# SCH_Atmega328-Dev_Board_v0_1_2022-11-11.net
KiCad netlist of a schematic drawn in EasyEDA
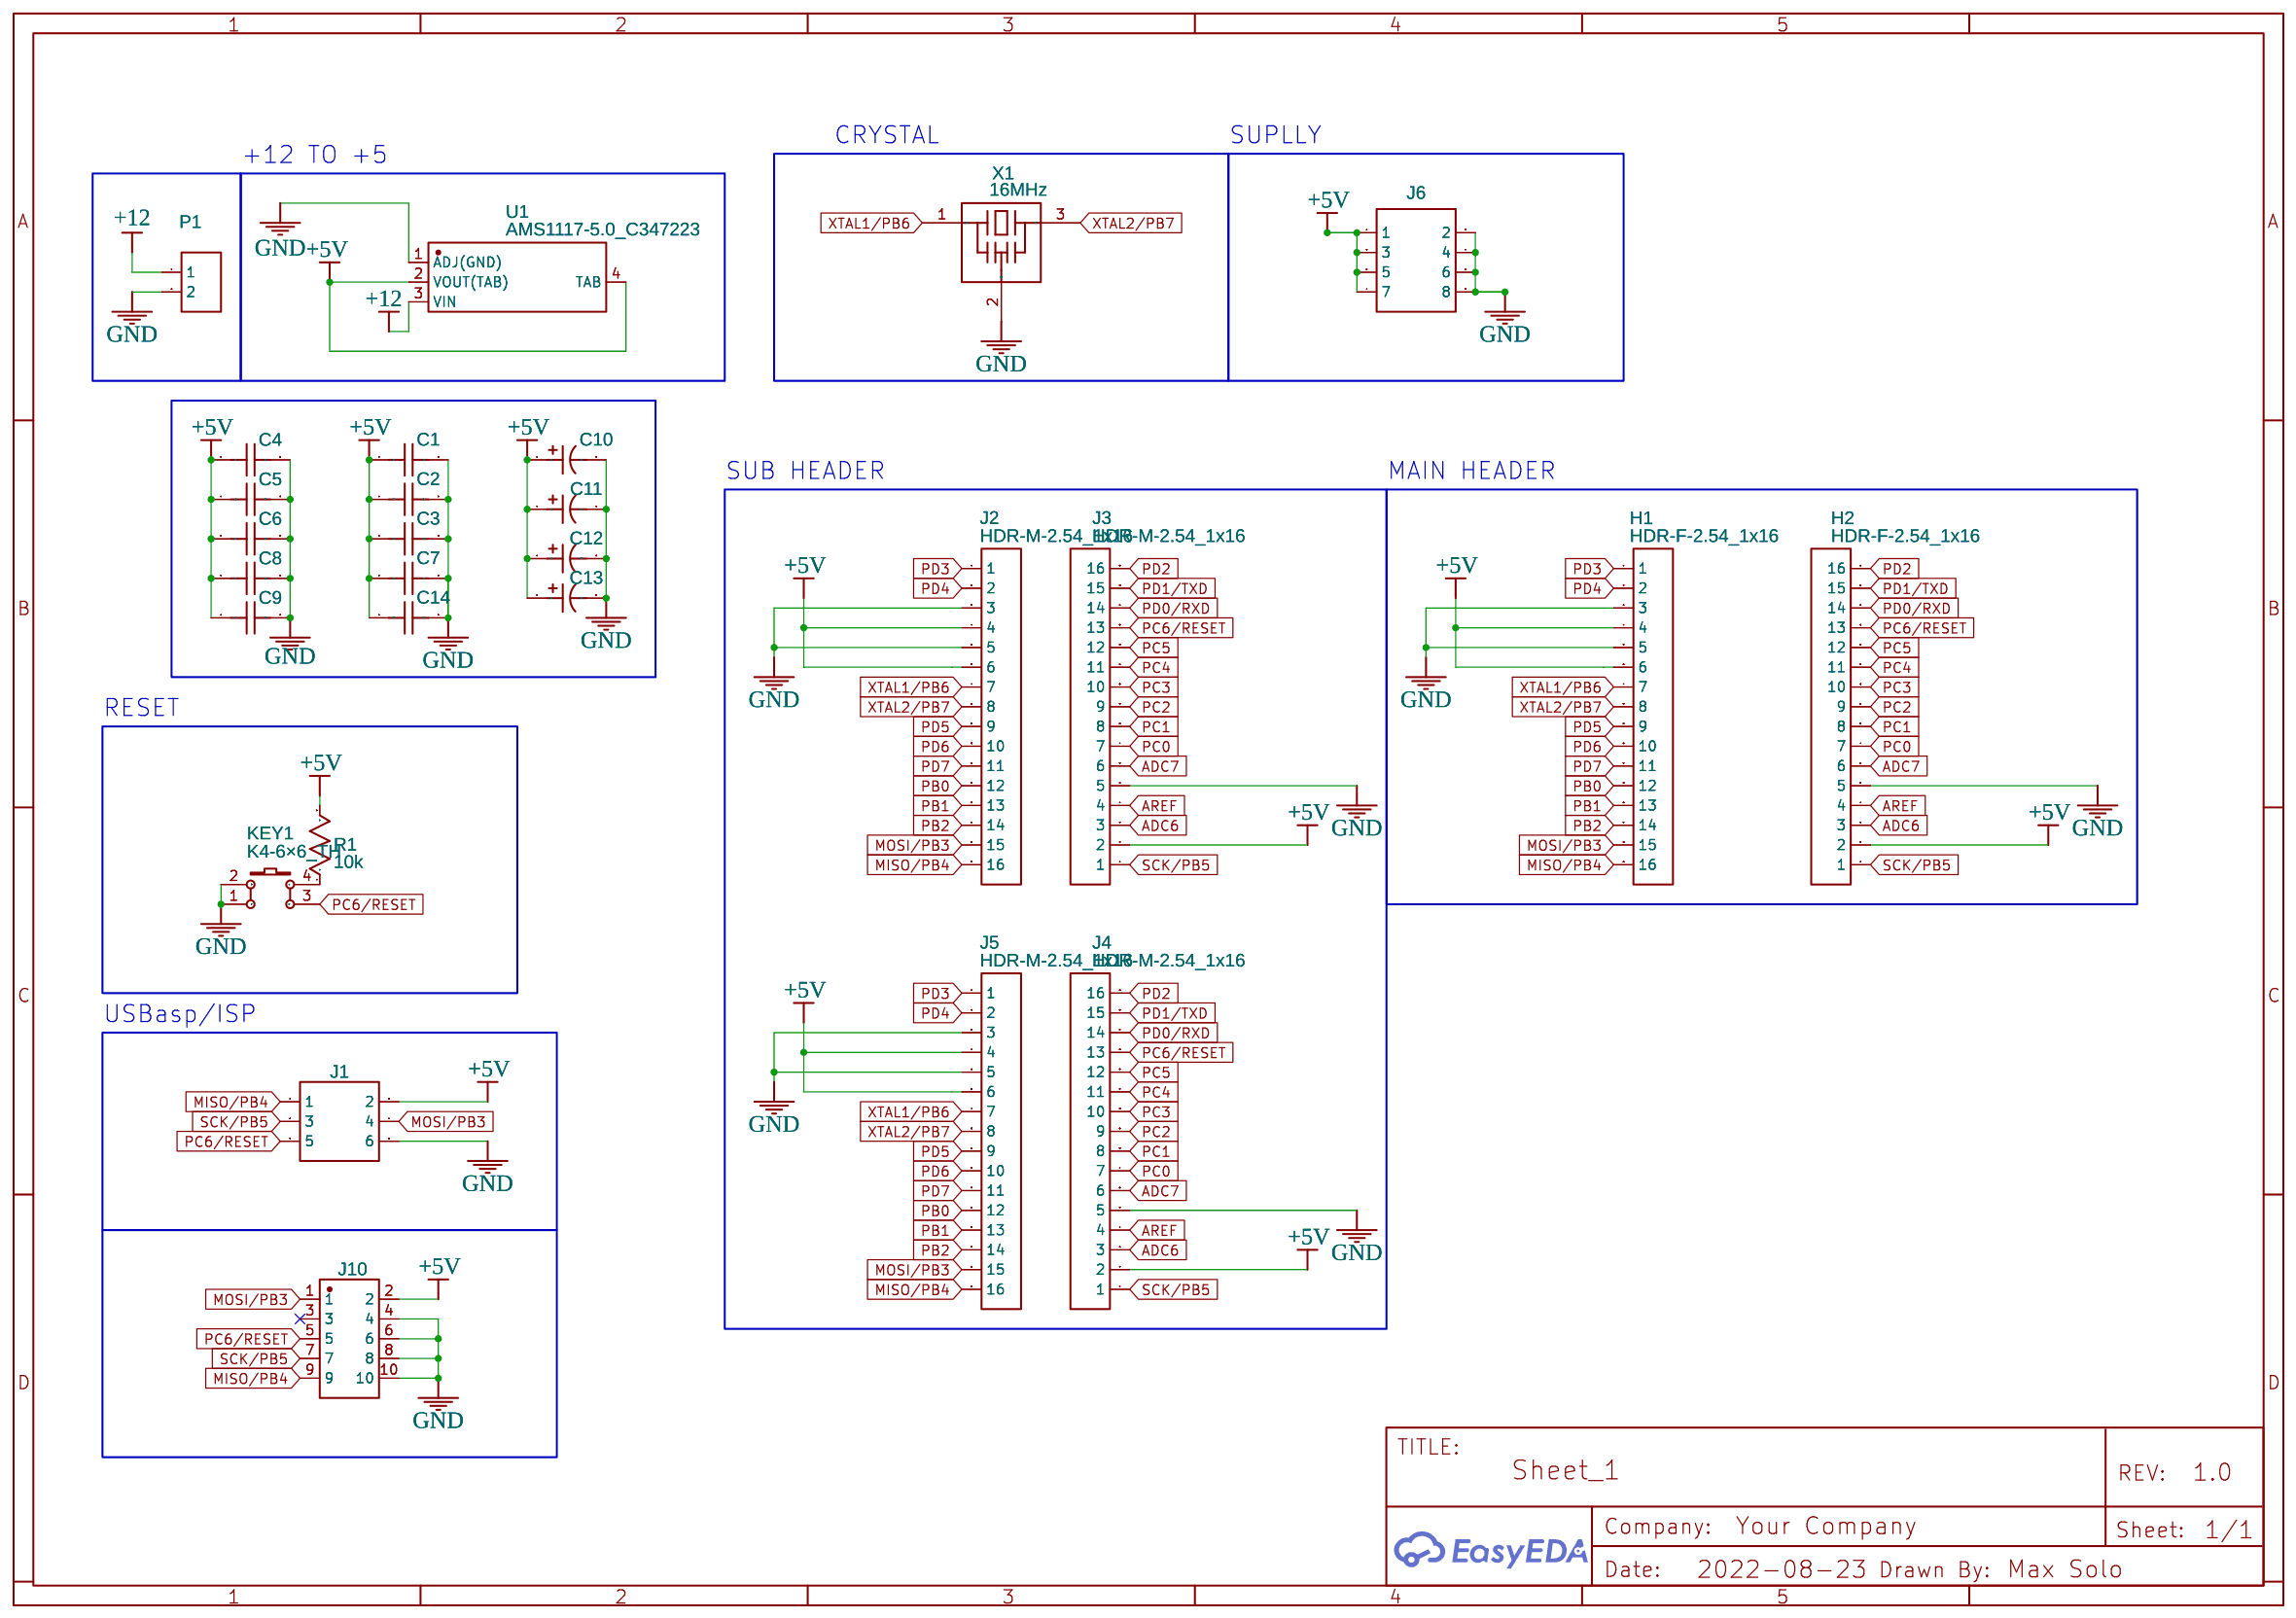
[diagram p0: schematic sheet]

(export (version "E")
  (design (tool "Eeschema 10.0.6"))
  (components
    (comp (ref "C1") (value "200uF") (libsource (lib "") (part "C_0805_US")))
    (comp (ref "C2") (value "200uF") (libsource (lib "") (part "C_0805_US")))
    (comp (ref "C3") (value "200uF") (libsource (lib "") (part "C_0805_US")))
    (comp (ref "C4") (value "200uF") (libsource (lib "") (part "C_0805_US")))
    (comp (ref "C5") (value "200uF") (libsource (lib "") (part "C_0805_US")))
    (comp (ref "C6") (value "200uF") (libsource (lib "") (part "C_0805_US")))
    (comp (ref "C7") (value "0.1u") (libsource (lib "") (part "C_0805_US")))
    (comp (ref "C8") (value "200uF") (libsource (lib "") (part "C_0805_US")))
    (comp (ref "C9") (value "200uF") (libsource (lib "") (part "C_0805_US")))
    (comp (ref "C10")
      (value "330uF")
      (fields
        (field (name "BOM_Manufacturer Part") "SPT1AM331E07OR")
        (field (name "BOM_Supplier Part") "C697724")
      )
      (libsource (lib "") (part "SPT1AM331E07OR"))
    )
    (comp (ref "C11")
      (value "330uF")
      (fields
        (field (name "BOM_Manufacturer Part") "SPT1AM331E07OR")
        (field (name "BOM_Supplier Part") "C697724")
      )
      (libsource (lib "") (part "SPT1AM331E07OR"))
    )
    (comp (ref "C12")
      (value "330uF")
      (fields
        (field (name "BOM_Manufacturer Part") "SPT1AM331E07OR")
        (field (name "BOM_Supplier Part") "C697724")
      )
      (libsource (lib "") (part "SPT1AM331E07OR"))
    )
    (comp (ref "C13")
      (value "330uF")
      (fields
        (field (name "BOM_Manufacturer Part") "SPT1AM331E07OR")
        (field (name "BOM_Supplier Part") "C697724")
      )
      (libsource (lib "") (part "SPT1AM331E07OR"))
    )
    (comp (ref "C14") (value "0.1u") (libsource (lib "") (part "C_0805_US")))
    (comp (ref "H1")
      (value "HDR-F-2.54_1x16")
      (fields (field (name "BOM_Supplier Part") "C66987"))
      (libsource (lib "") (part "HDR-F-2.54_1x16"))
    )
    (comp (ref "H2")
      (value "HDR-F-2.54_1x16")
      (fields (field (name "BOM_Supplier Part") "C66987"))
      (libsource (lib "") (part "HDR-F-2.54_1x16_1"))
    )
    (comp (ref "J1")
      (value "HDR-M-2.54_2x3")
      (fields (field (name "BOM_Supplier Part") "C65114"))
      (libsource (lib "") (part "HDR-M-2.54_2x3"))
    )
    (comp (ref "J2") (value "HDR-M-2.54_1x16") (libsource (lib "") (part "HDR-M-2.54_1x16")))
    (comp (ref "J3") (value "HDR-M-2.54_1x16") (libsource (lib "") (part "HDR-M-2.54_1x16_1")))
    (comp (ref "J4") (value "HDR-M-2.54_1x16") (libsource (lib "") (part "HDR-M-2.54_1x16_1")))
    (comp (ref "J5") (value "HDR-M-2.54_1x16") (libsource (lib "") (part "HDR-M-2.54_1x16")))
    (comp (ref "J6")
      (value "HDR-M-2.54_2x4")
      (fields (field (name "BOM_Supplier Part") "C58363"))
      (libsource (lib "") (part "HDR-M-2.54_2x4"))
    )
    (comp (ref "J10")
      (value "X2530WV-2X05-PTSN")
      (fields
        (field (name "BOM_Manufacturer Part") "X2530WV-2x05-PTSN")
        (field (name "BOM_Supplier Part") "C2882570")
      )
      (libsource (lib "") (part "X2530WV-2X05-PTSN"))
    )
    (comp (ref "KEY1")
      (value "K4-6×6_TH")
      (fields
        (field (name "BOM_Manufacturer Part") "K2-1102DP-E4SW-04")
        (field (name "BOM_Supplier Part") "C136684")
      )
      (libsource (lib "") (part "K4-6×6_TH"))
    )
    (comp (ref "P1") (value "CONN-TH_2P-P5.00") (libsource (lib "") (part "CONN-TH_2P-P5.00")))
    (comp (ref "R1") (value "10k") (libsource (lib "") (part "R_0805_US")))
    (comp (ref "U1")
      (value "AMS1117-5.0_C347223")
      (fields
        (field (name "BOM_Manufacturer Part") "AMS1117-5.0")
        (field (name "BOM_Supplier Part") "C347223")
      )
      (libsource (lib "") (part "AMS1117-5.0_C347223"))
    )
    (comp (ref "X1")
      (value "16MHz")
      (fields
        (field (name "BOM_Manufacturer Part") "CSTCE16M0V13C99-R0")
        (field (name "BOM_Supplier Part") "C118038")
      )
      (libsource (lib "") (part "CSTCE16M0V13C99-R0"))
    )
  )
  (nets
    (net (code "1") (name "+5V") (class "Default")
      (node (ref "C1") (pin "1") (pinfunction "1_1") (pintype "unspecified"))
      (node (ref "C10") (pin "1") (pinfunction "1_1") (pintype "input"))
      (node (ref "C11") (pin "1") (pinfunction "1_1") (pintype "input"))
      (node (ref "C12") (pin "1") (pinfunction "1_1") (pintype "input"))
      (node (ref "C13") (pin "1") (pinfunction "1_1") (pintype "input"))
      (node (ref "C14") (pin "1") (pinfunction "1_1") (pintype "unspecified"))
      (node (ref "C2") (pin "1") (pinfunction "1_1") (pintype "unspecified"))
      (node (ref "C3") (pin "1") (pinfunction "1_1") (pintype "unspecified"))
      (node (ref "C4") (pin "1") (pinfunction "1_1") (pintype "unspecified"))
      (node (ref "C5") (pin "1") (pinfunction "1_1") (pintype "unspecified"))
      (node (ref "C6") (pin "1") (pinfunction "1_1") (pintype "unspecified"))
      (node (ref "C7") (pin "1") (pinfunction "1_1") (pintype "unspecified"))
      (node (ref "C8") (pin "1") (pinfunction "1_1") (pintype "unspecified"))
      (node (ref "C9") (pin "1") (pinfunction "1_1") (pintype "unspecified"))
      (node (ref "H1") (pin "4") (pinfunction "4_4") (pintype "unspecified"))
      (node (ref "H1") (pin "6") (pinfunction "6_6") (pintype "unspecified"))
      (node (ref "H2") (pin "2") (pinfunction "2_2") (pintype "unspecified"))
      (node (ref "J1") (pin "2") (pinfunction "2_2") (pintype "input"))
      (node (ref "J10") (pin "2") (pinfunction "2_2") (pintype "unspecified"))
      (node (ref "J2") (pin "4") (pinfunction "4_4") (pintype "unspecified"))
      (node (ref "J2") (pin "6") (pinfunction "6_6") (pintype "unspecified"))
      (node (ref "J3") (pin "2") (pinfunction "2_2") (pintype "unspecified"))
      (node (ref "J4") (pin "2") (pinfunction "2_2") (pintype "unspecified"))
      (node (ref "J5") (pin "4") (pinfunction "4_4") (pintype "unspecified"))
      (node (ref "J5") (pin "6") (pinfunction "6_6") (pintype "unspecified"))
      (node (ref "J6") (pin "1") (pinfunction "1_1") (pintype "unspecified"))
      (node (ref "J6") (pin "3") (pinfunction "3_3") (pintype "unspecified"))
      (node (ref "J6") (pin "5") (pinfunction "5_5") (pintype "unspecified"))
      (node (ref "J6") (pin "7") (pinfunction "7_7") (pintype "unspecified"))
      (node (ref "R1") (pin "2") (pinfunction "2_2") (pintype "unspecified"))
      (node (ref "U1") (pin "2") (pinfunction "VOUT(TAB)_2") (pintype "unspecified"))
      (node (ref "U1") (pin "4") (pinfunction "TAB_4") (pintype "unspecified"))
    )
    (net (code "2") (name "+12") (class "Default")
      (node (ref "P1") (pin "1") (pinfunction "1_1") (pintype "unspecified"))
      (node (ref "U1") (pin "3") (pinfunction "VIN_3") (pintype "unspecified"))
    )
    (net (code "3") (name "ADC6") (class "Default")
      (node (ref "H2") (pin "3") (pinfunction "3_3") (pintype "unspecified"))
      (node (ref "J3") (pin "3") (pinfunction "3_3") (pintype "unspecified"))
      (node (ref "J4") (pin "3") (pinfunction "3_3") (pintype "unspecified"))
    )
    (net (code "4") (name "ADC7") (class "Default")
      (node (ref "H2") (pin "6") (pinfunction "6_6") (pintype "unspecified"))
      (node (ref "J3") (pin "6") (pinfunction "6_6") (pintype "unspecified"))
      (node (ref "J4") (pin "6") (pinfunction "6_6") (pintype "unspecified"))
    )
    (net (code "5") (name "AREF") (class "Default")
      (node (ref "H2") (pin "4") (pinfunction "4_4") (pintype "unspecified"))
      (node (ref "J3") (pin "4") (pinfunction "4_4") (pintype "unspecified"))
      (node (ref "J4") (pin "4") (pinfunction "4_4") (pintype "unspecified"))
    )
    (net (code "6") (name "GND") (class "Default")
      (node (ref "C1") (pin "2") (pinfunction "2_2") (pintype "unspecified"))
      (node (ref "C10") (pin "2") (pinfunction "2_2") (pintype "input"))
      (node (ref "C11") (pin "2") (pinfunction "2_2") (pintype "input"))
      (node (ref "C12") (pin "2") (pinfunction "2_2") (pintype "input"))
      (node (ref "C13") (pin "2") (pinfunction "2_2") (pintype "input"))
      (node (ref "C14") (pin "2") (pinfunction "2_2") (pintype "unspecified"))
      (node (ref "C2") (pin "2") (pinfunction "2_2") (pintype "unspecified"))
      (node (ref "C3") (pin "2") (pinfunction "2_2") (pintype "unspecified"))
      (node (ref "C4") (pin "2") (pinfunction "2_2") (pintype "unspecified"))
      (node (ref "C5") (pin "2") (pinfunction "2_2") (pintype "unspecified"))
      (node (ref "C6") (pin "2") (pinfunction "2_2") (pintype "unspecified"))
      (node (ref "C7") (pin "2") (pinfunction "2_2") (pintype "unspecified"))
      (node (ref "C8") (pin "2") (pinfunction "2_2") (pintype "unspecified"))
      (node (ref "C9") (pin "2") (pinfunction "2_2") (pintype "unspecified"))
      (node (ref "H1") (pin "3") (pinfunction "3_3") (pintype "unspecified"))
      (node (ref "H1") (pin "5") (pinfunction "5_5") (pintype "unspecified"))
      (node (ref "H2") (pin "5") (pinfunction "5_5") (pintype "unspecified"))
      (node (ref "J1") (pin "6") (pinfunction "6_6") (pintype "input"))
      (node (ref "J10") (pin "10") (pinfunction "10_10") (pintype "unspecified"))
      (node (ref "J10") (pin "4") (pinfunction "4_4") (pintype "unspecified"))
      (node (ref "J10") (pin "6") (pinfunction "6_6") (pintype "unspecified"))
      (node (ref "J10") (pin "8") (pinfunction "8_8") (pintype "unspecified"))
      (node (ref "J2") (pin "3") (pinfunction "3_3") (pintype "unspecified"))
      (node (ref "J2") (pin "5") (pinfunction "5_5") (pintype "unspecified"))
      (node (ref "J3") (pin "5") (pinfunction "5_5") (pintype "unspecified"))
      (node (ref "J4") (pin "5") (pinfunction "5_5") (pintype "unspecified"))
      (node (ref "J5") (pin "3") (pinfunction "3_3") (pintype "unspecified"))
      (node (ref "J5") (pin "5") (pinfunction "5_5") (pintype "unspecified"))
      (node (ref "J6") (pin "2") (pinfunction "2_2") (pintype "unspecified"))
      (node (ref "J6") (pin "4") (pinfunction "4_4") (pintype "unspecified"))
      (node (ref "J6") (pin "6") (pinfunction "6_6") (pintype "unspecified"))
      (node (ref "J6") (pin "8") (pinfunction "8_8") (pintype "unspecified"))
      (node (ref "KEY1") (pin "1") (pinfunction "1_1") (pintype "unspecified"))
      (node (ref "KEY1") (pin "2") (pinfunction "2_2") (pintype "unspecified"))
      (node (ref "P1") (pin "2") (pinfunction "2_2") (pintype "unspecified"))
      (node (ref "U1") (pin "1") (pinfunction "ADJ(GND)_1") (pintype "unspecified"))
      (node (ref "X1") (pin "2") (pinfunction "VSS_2") (pintype "passive"))
    )
    (net (code "7") (name "MISO{slash}PB4") (class "Default")
      (node (ref "H1") (pin "16") (pinfunction "16_16") (pintype "unspecified"))
      (node (ref "J1") (pin "1") (pinfunction "1_1") (pintype "input"))
      (node (ref "J10") (pin "9") (pinfunction "9_9") (pintype "unspecified"))
      (node (ref "J2") (pin "16") (pinfunction "16_16") (pintype "unspecified"))
      (node (ref "J5") (pin "16") (pinfunction "16_16") (pintype "unspecified"))
    )
    (net (code "8") (name "MOSI{slash}PB3") (class "Default")
      (node (ref "H1") (pin "15") (pinfunction "15_15") (pintype "unspecified"))
      (node (ref "J1") (pin "4") (pinfunction "4_4") (pintype "input"))
      (node (ref "J10") (pin "1") (pinfunction "1_1") (pintype "unspecified"))
      (node (ref "J2") (pin "15") (pinfunction "15_15") (pintype "unspecified"))
      (node (ref "J5") (pin "15") (pinfunction "15_15") (pintype "unspecified"))
    )
    (net (code "9") (name "Net-(KEY1-Pad4)") (class "Default")
      (node (ref "KEY1") (pin "4") (pinfunction "4_4") (pintype "unspecified"))
      (node (ref "R1") (pin "1") (pinfunction "1_1") (pintype "unspecified"))
    )
    (net (code "10") (name "PB0") (class "Default")
      (node (ref "H1") (pin "12") (pinfunction "12_12") (pintype "unspecified"))
      (node (ref "J2") (pin "12") (pinfunction "12_12") (pintype "unspecified"))
      (node (ref "J5") (pin "12") (pinfunction "12_12") (pintype "unspecified"))
    )
    (net (code "11") (name "PB1") (class "Default")
      (node (ref "H1") (pin "13") (pinfunction "13_13") (pintype "unspecified"))
      (node (ref "J2") (pin "13") (pinfunction "13_13") (pintype "unspecified"))
      (node (ref "J5") (pin "13") (pinfunction "13_13") (pintype "unspecified"))
    )
    (net (code "12") (name "PB2") (class "Default")
      (node (ref "H1") (pin "14") (pinfunction "14_14") (pintype "unspecified"))
      (node (ref "J2") (pin "14") (pinfunction "14_14") (pintype "unspecified"))
      (node (ref "J5") (pin "14") (pinfunction "14_14") (pintype "unspecified"))
    )
    (net (code "13") (name "PC0") (class "Default")
      (node (ref "H2") (pin "7") (pinfunction "7_7") (pintype "unspecified"))
      (node (ref "J3") (pin "7") (pinfunction "7_7") (pintype "unspecified"))
      (node (ref "J4") (pin "7") (pinfunction "7_7") (pintype "unspecified"))
    )
    (net (code "14") (name "PC1") (class "Default")
      (node (ref "H2") (pin "8") (pinfunction "8_8") (pintype "unspecified"))
      (node (ref "J3") (pin "8") (pinfunction "8_8") (pintype "unspecified"))
      (node (ref "J4") (pin "8") (pinfunction "8_8") (pintype "unspecified"))
    )
    (net (code "15") (name "PC2") (class "Default")
      (node (ref "H2") (pin "9") (pinfunction "9_9") (pintype "unspecified"))
      (node (ref "J3") (pin "9") (pinfunction "9_9") (pintype "unspecified"))
      (node (ref "J4") (pin "9") (pinfunction "9_9") (pintype "unspecified"))
    )
    (net (code "16") (name "PC3") (class "Default")
      (node (ref "H2") (pin "10") (pinfunction "10_10") (pintype "unspecified"))
      (node (ref "J3") (pin "10") (pinfunction "10_10") (pintype "unspecified"))
      (node (ref "J4") (pin "10") (pinfunction "10_10") (pintype "unspecified"))
    )
    (net (code "17") (name "PC4") (class "Default")
      (node (ref "H2") (pin "11") (pinfunction "11_11") (pintype "unspecified"))
      (node (ref "J3") (pin "11") (pinfunction "11_11") (pintype "unspecified"))
      (node (ref "J4") (pin "11") (pinfunction "11_11") (pintype "unspecified"))
    )
    (net (code "18") (name "PC5") (class "Default")
      (node (ref "H2") (pin "12") (pinfunction "12_12") (pintype "unspecified"))
      (node (ref "J3") (pin "12") (pinfunction "12_12") (pintype "unspecified"))
      (node (ref "J4") (pin "12") (pinfunction "12_12") (pintype "unspecified"))
    )
    (net (code "19") (name "PC6{slash}RESET") (class "Default")
      (node (ref "H2") (pin "13") (pinfunction "13_13") (pintype "unspecified"))
      (node (ref "J1") (pin "5") (pinfunction "5_5") (pintype "input"))
      (node (ref "J10") (pin "5") (pinfunction "5_5") (pintype "unspecified"))
      (node (ref "J3") (pin "13") (pinfunction "13_13") (pintype "unspecified"))
      (node (ref "J4") (pin "13") (pinfunction "13_13") (pintype "unspecified"))
      (node (ref "KEY1") (pin "3") (pinfunction "3_3") (pintype "unspecified"))
    )
    (net (code "20") (name "PD0{slash}RXD") (class "Default")
      (node (ref "H2") (pin "14") (pinfunction "14_14") (pintype "unspecified"))
      (node (ref "J3") (pin "14") (pinfunction "14_14") (pintype "unspecified"))
      (node (ref "J4") (pin "14") (pinfunction "14_14") (pintype "unspecified"))
    )
    (net (code "21") (name "PD1{slash}TXD") (class "Default")
      (node (ref "H2") (pin "15") (pinfunction "15_15") (pintype "unspecified"))
      (node (ref "J3") (pin "15") (pinfunction "15_15") (pintype "unspecified"))
      (node (ref "J4") (pin "15") (pinfunction "15_15") (pintype "unspecified"))
    )
    (net (code "22") (name "PD2") (class "Default")
      (node (ref "H2") (pin "16") (pinfunction "16_16") (pintype "unspecified"))
      (node (ref "J3") (pin "16") (pinfunction "16_16") (pintype "unspecified"))
      (node (ref "J4") (pin "16") (pinfunction "16_16") (pintype "unspecified"))
    )
    (net (code "23") (name "PD3") (class "Default")
      (node (ref "H1") (pin "1") (pinfunction "1_1") (pintype "unspecified"))
      (node (ref "J2") (pin "1") (pinfunction "1_1") (pintype "unspecified"))
      (node (ref "J5") (pin "1") (pinfunction "1_1") (pintype "unspecified"))
    )
    (net (code "24") (name "PD4") (class "Default")
      (node (ref "H1") (pin "2") (pinfunction "2_2") (pintype "unspecified"))
      (node (ref "J2") (pin "2") (pinfunction "2_2") (pintype "unspecified"))
      (node (ref "J5") (pin "2") (pinfunction "2_2") (pintype "unspecified"))
    )
    (net (code "25") (name "PD5") (class "Default")
      (node (ref "H1") (pin "9") (pinfunction "9_9") (pintype "unspecified"))
      (node (ref "J2") (pin "9") (pinfunction "9_9") (pintype "unspecified"))
      (node (ref "J5") (pin "9") (pinfunction "9_9") (pintype "unspecified"))
    )
    (net (code "26") (name "PD6") (class "Default")
      (node (ref "H1") (pin "10") (pinfunction "10_10") (pintype "unspecified"))
      (node (ref "J2") (pin "10") (pinfunction "10_10") (pintype "unspecified"))
      (node (ref "J5") (pin "10") (pinfunction "10_10") (pintype "unspecified"))
    )
    (net (code "27") (name "PD7") (class "Default")
      (node (ref "H1") (pin "11") (pinfunction "11_11") (pintype "unspecified"))
      (node (ref "J2") (pin "11") (pinfunction "11_11") (pintype "unspecified"))
      (node (ref "J5") (pin "11") (pinfunction "11_11") (pintype "unspecified"))
    )
    (net (code "28") (name "SCK{slash}PB5") (class "Default")
      (node (ref "H2") (pin "1") (pinfunction "1_1") (pintype "unspecified"))
      (node (ref "J1") (pin "3") (pinfunction "3_3") (pintype "input"))
      (node (ref "J10") (pin "7") (pinfunction "7_7") (pintype "unspecified"))
      (node (ref "J3") (pin "1") (pinfunction "1_1") (pintype "unspecified"))
      (node (ref "J4") (pin "1") (pinfunction "1_1") (pintype "unspecified"))
    )
    (net (code "29") (name "XTAL1{slash}PB6") (class "Default")
      (node (ref "H1") (pin "7") (pinfunction "7_7") (pintype "unspecified"))
      (node (ref "J2") (pin "7") (pinfunction "7_7") (pintype "unspecified"))
      (node (ref "J5") (pin "7") (pinfunction "7_7") (pintype "unspecified"))
      (node (ref "X1") (pin "1") (pinfunction "1_1") (pintype "output"))
    )
    (net (code "30") (name "XTAL2{slash}PB7") (class "Default")
      (node (ref "H1") (pin "8") (pinfunction "8_8") (pintype "unspecified"))
      (node (ref "J2") (pin "8") (pinfunction "8_8") (pintype "unspecified"))
      (node (ref "J5") (pin "8") (pinfunction "8_8") (pintype "unspecified"))
      (node (ref "X1") (pin "3") (pinfunction "3_3") (pintype "input"))
    )
    (net (code "31") (name "unconnected-(J10-Pad3)") (class "Default")
      (node (ref "J10") (pin "3") (pinfunction "3_3") (pintype "unspecified+no_connect"))
    )
  )
)
